# cd_switching.net
KiCad netlist of a schematic drawn in Altium Designer
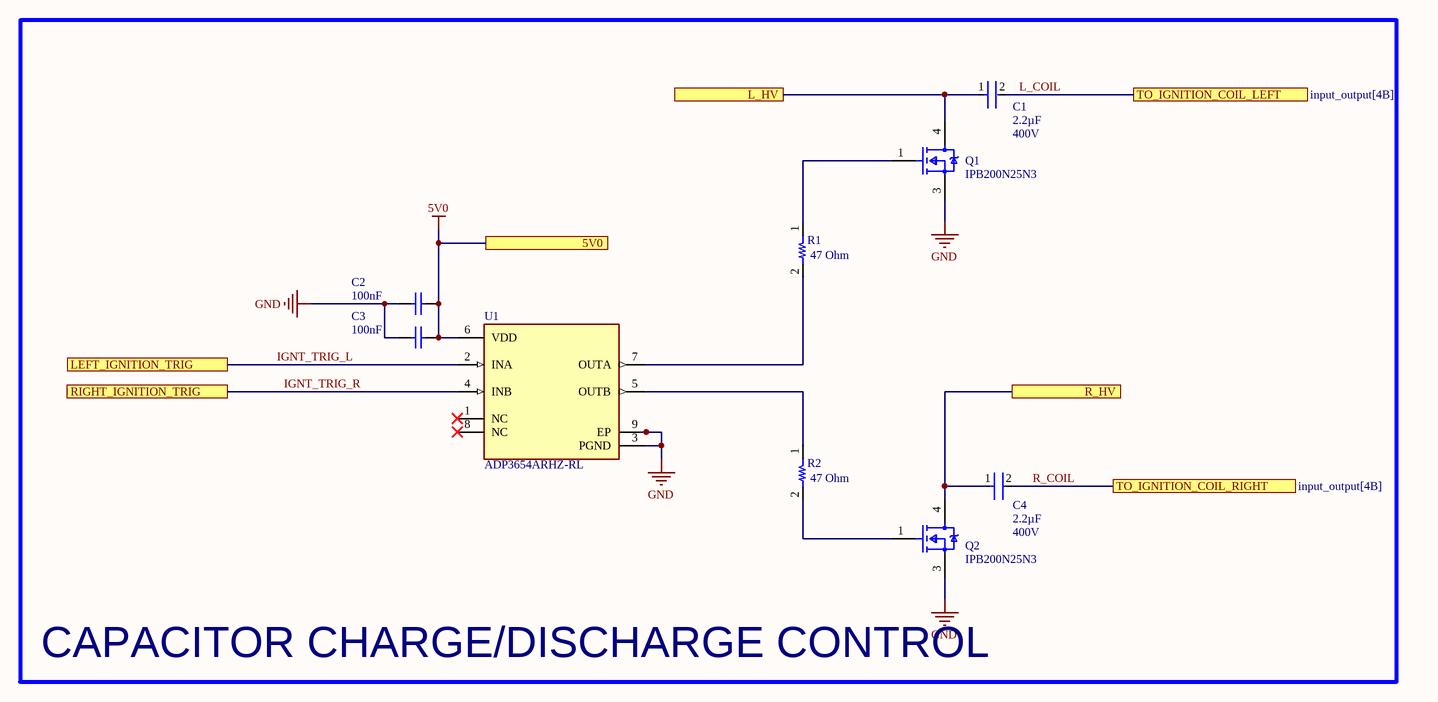
[diagram p0: cd_switching.SchDoc]

(export (version "E")
  (design (tool "Eeschema 10.0.6"))
  (components
    (comp (ref "C1")
      (value "BFC233820225")
      (footprint "FP-BFC233820225-MFG")
      (description "BFC233820225 Film Capacitor, Polypropylene, 800V, 20% +Tol, 20% -Tol, 0.22uF, Through Hole Mount")
      (fields
        (field (name "VOLTAGE RATING (AC)") "400V")
        (field (name "CAPACITANCE") "2.2µF")
        (field (name "TOLERANCE") "20%")
      )
      (libsource (lib "Altium Content Vault") (part "02cd4be3c70576c341d710602a673aa"))
    )
    (comp (ref "C2")
      (value "100nF")
      (footprint "CAPC1608X90X35LL15T15")
      (fields
        (field (name "MANUFACTURER") "AVX Interconnect / Elco")
        (field (name "PART NUMBER") "06035C104KAT4A")
      )
      (libsource (lib "Altium Content Vault") (part "CAP"))
    )
    (comp (ref "C3")
      (value "100nF")
      (footprint "CAPC1608X87X35NL15T15")
      (fields (field (name "PART NUMBER") "C0603C475K8PACTU") (field (name "MANUFACTURER") "Kemet"))
      (libsource (lib "Altium Content Vault") (part "CAP"))
    )
    (comp (ref "C4")
      (value "BFC233820225")
      (footprint "FP-BFC233820225-MFG")
      (description "BFC233820225 Film Capacitor, Polypropylene, 800V, 20% +Tol, 20% -Tol, 0.22uF, Through Hole Mount")
      (fields
        (field (name "VOLTAGE RATING (AC)") "400V")
        (field (name "CAPACITANCE") "2.2µF")
        (field (name "TOLERANCE") "20%")
      )
      (libsource (lib "Altium Content Vault") (part "02cd4be3c70576c341d710602a673aa"))
    )
    (comp (ref "Q1")
      (value "IPB200N25N3")
      (footprint "FP-PG-TO252-3-MFG")
      (description "MOSFET N-CH 30V 161A DPAK")
      (fields
        (field (name "OCTOPART") "https://octopart.com/irlr7843trpbf-infineon-65875062")
        (field (name "MANUFACTURER PART NUMBER") "IRLR7843TRPBF")
      )
      (libsource (lib "Altium Content Vault") (part "2f21c11e83d30f418bb422e5a3b3d11"))
    )
    (comp (ref "Q2")
      (value "IPB200N25N3")
      (footprint "FP-PG-TO252-3-MFG")
      (description "MOSFET N-CH 30V 161A DPAK")
      (fields
        (field (name "OCTOPART") "https://octopart.com/irlr7843trpbf-infineon-65875062")
        (field (name "MANUFACTURER PART NUMBER") "IRLR7843TRPBF")
      )
      (libsource (lib "Altium Content Vault") (part "2f21c11e83d30f418bb422e5a3b3d11"))
    )
    (comp (ref "R1")
      (value "47 Ohm")
      (footprint "0603_FP")
      (fields (field (name "Comment") "Resistor_0603"))
      (libsource (lib "RC_sch") (part "Resistor_0603"))
    )
    (comp (ref "R2")
      (value "47 Ohm")
      (footprint "0603_FP")
      (fields (field (name "Comment") "Resistor_0603"))
      (libsource (lib "RC_sch") (part "Resistor_0603"))
    )
    (comp (ref "U1")
      (value "ADP3654ARHZ-RL")
      (footprint "FP-RH-8-1-IPC_C")
      (description "IC GATE DRVR LOW-SIDE 8MINISOIC")
      (libsource (lib "Altium Content Vault") (part "30ea4086147ff647bd0a3436ecf34e5"))
    )
  )
  (nets
    (net (code "1") (name "/IGNT_TRIG_L") (class "Default")
      (node (ref "U1") (pin "2") (pinfunction "INA_2") (pintype "input"))
    )
    (net (code "2") (name "/IGNT_TRIG_R") (class "Default")
      (node (ref "U1") (pin "4") (pinfunction "INB_4") (pintype "input"))
    )
    (net (code "3") (name "/L_COIL") (class "Default")
      (node (ref "C1") (pin "2") (pinfunction "2_2") (pintype "passive"))
    )
    (net (code "4") (name "/L_HV") (class "Default")
      (node (ref "C1") (pin "1") (pinfunction "1_1") (pintype "passive"))
      (node (ref "Q1") (pin "4") (pinfunction "DRAIN_4") (pintype "passive"))
    )
    (net (code "5") (name "/R_COIL") (class "Default")
      (node (ref "C4") (pin "2") (pinfunction "2_2") (pintype "passive"))
    )
    (net (code "6") (name "/R_HV") (class "Default")
      (node (ref "C4") (pin "1") (pinfunction "1_1") (pintype "passive"))
      (node (ref "Q2") (pin "4") (pinfunction "DRAIN_4") (pintype "passive"))
    )
    (net (code "7") (name "5V0") (class "Default")
      (node (ref "C2") (pin "1") (pinfunction "1_1") (pintype "passive"))
      (node (ref "C3") (pin "2") (pinfunction "2_2") (pintype "passive"))
      (node (ref "U1") (pin "6") (pinfunction "VDD_6") (pintype "power_in"))
    )
    (net (code "8") (name "GND") (class "Default")
      (node (ref "C2") (pin "2") (pinfunction "2_2") (pintype "passive"))
      (node (ref "C3") (pin "1") (pinfunction "1_1") (pintype "passive"))
      (node (ref "Q1") (pin "3") (pinfunction "SOURCE_3") (pintype "passive"))
      (node (ref "Q2") (pin "3") (pinfunction "SOURCE_3") (pintype "passive"))
      (node (ref "U1") (pin "3") (pinfunction "PGND_3") (pintype "power_in"))
      (node (ref "U1") (pin "9") (pinfunction "EP_9") (pintype "power_in"))
    )
    (net (code "9") (name "Net-(Q1-GATE)") (class "Default")
      (node (ref "Q1") (pin "1") (pinfunction "GATE_1") (pintype "passive"))
      (node (ref "R1") (pin "1") (pinfunction "1_1") (pintype "passive"))
    )
    (net (code "10") (name "Net-(Q2-GATE)") (class "Default")
      (node (ref "Q2") (pin "1") (pinfunction "GATE_1") (pintype "passive"))
      (node (ref "R2") (pin "2") (pinfunction "2_2") (pintype "passive"))
    )
    (net (code "11") (name "Net-(U1-OUTA)") (class "Default")
      (node (ref "R1") (pin "2") (pinfunction "2_2") (pintype "passive"))
      (node (ref "U1") (pin "7") (pinfunction "OUTA_7") (pintype "output"))
    )
    (net (code "12") (name "Net-(U1-OUTB)") (class "Default")
      (node (ref "R2") (pin "1") (pinfunction "1_1") (pintype "passive"))
      (node (ref "U1") (pin "5") (pinfunction "OUTB_5") (pintype "output"))
    )
    (net (code "13") (name "unconnected-(U1-NC-Pad1)") (class "Default")
      (node (ref "U1") (pin "1") (pinfunction "NC_1") (pintype "passive+no_connect"))
    )
    (net (code "14") (name "unconnected-(U1-NC-Pad8)") (class "Default")
      (node (ref "U1") (pin "8") (pinfunction "NC_8") (pintype "passive+no_connect"))
    )
  )
)
